# PIC_Schematic.net
KiCad netlist of a schematic drawn in Altium Designer
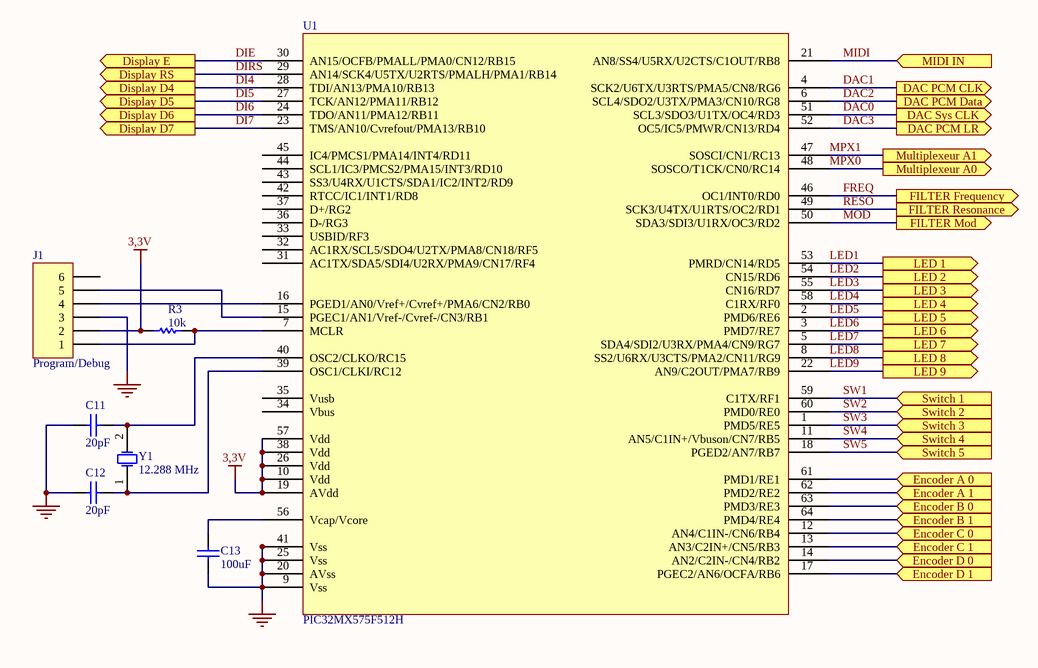
[diagram p0: PIC.Schematic.SchDoc]

(export (version "E")
  (design (tool "Eeschema 10.0.6"))
  (components
    (comp (ref "C11")
      (value "20pF")
      (footprint "CAP1608N")
      (description "Capacitor (Semiconductor SIM Model)")
      (fields (field (name "PUBLISHER") "Altium Limited"))
      (libsource (lib "Miscellaneous Devices") (part "Cap Semi"))
    )
    (comp (ref "C12")
      (value "20pF")
      (footprint "CAP1608N")
      (description "Capacitor (Semiconductor SIM Model)")
      (fields (field (name "PUBLISHER") "Altium Limited"))
      (libsource (lib "Miscellaneous Devices") (part "Cap Semi"))
    )
    (comp (ref "C13")
      (value "100uF")
      (footprint "RAD-0.3")
      (description "Capacitor")
      (fields (field (name "Comment") "Cap") (field (name "PUBLISHER") "Altium Limited"))
      (libsource (lib "Miscellaneous Devices") (part "Cap"))
    )
    (comp (ref "J1")
      (value "Program/Debug")
      (footprint "HDR1X6H")
      (description "Header, 6-Pin, Right Angle")
      (fields (field (name "PUBLISHER") "Altium Limited"))
      (libsource (lib "Miscellaneous Connectors") (part "Header 6H"))
    )
    (comp (ref "R3")
      (value "10k")
      (footprint "AXIAL-0.3")
      (description "Resistor")
      (fields (field (name "PUBLISHER") "Altium Limited"))
      (libsource (lib "Miscellaneous Devices") (part "Res1"))
    )
    (comp (ref "U1")
      (value "PIC32MX575F512H")
      (libsource (lib "SynthyTwo.Components") (part "PIC32 MX575F512H"))
    )
    (comp (ref "Y1")
      (value "12.288 MHz")
      (footprint "R38")
      (description "Crystal Oscillator")
      (fields (field (name "PUBLISHER") "Altium Limited"))
      (libsource (lib "Miscellaneous Devices") (part "XTAL"))
    )
  )
  (nets
    (net (code "1") (name "/DAC0") (class "Default")
      (node (ref "U1") (pin "51") (pinfunction "SCL3/SDO3/U1TX/OC4/RD3_51") (pintype "passive"))
    )
    (net (code "2") (name "/DAC1") (class "Default")
      (node (ref "U1") (pin "4") (pinfunction "SCK2/U6TX/U3RTS/PMA5/CN8/RG6_4") (pintype "passive"))
    )
    (net (code "3") (name "/DAC2") (class "Default")
      (node (ref "U1") (pin "6") (pinfunction "SCL4/SDO2/U3TX/PMA3/CN10/RG8_6") (pintype "passive"))
    )
    (net (code "4") (name "/DAC3") (class "Default")
      (node (ref "U1") (pin "52") (pinfunction "OC5/IC5/PMWR/CN13/RD4_52") (pintype "passive"))
    )
    (net (code "5") (name "/DI4") (class "Default")
      (node (ref "U1") (pin "28") (pinfunction "TDI/AN13/PMA10/RB13_28") (pintype "passive"))
    )
    (net (code "6") (name "/DI5") (class "Default")
      (node (ref "U1") (pin "27") (pinfunction "TCK/AN12/PMA11/RB12_27") (pintype "passive"))
    )
    (net (code "7") (name "/DI6") (class "Default")
      (node (ref "U1") (pin "24") (pinfunction "TDO/AN11/PMA12/RB11_24") (pintype "passive"))
    )
    (net (code "8") (name "/DI7") (class "Default")
      (node (ref "U1") (pin "23") (pinfunction "TMS/AN10/Cvrefout/PMA13/RB10_23") (pintype "passive"))
    )
    (net (code "9") (name "/DIE") (class "Default")
      (node (ref "U1") (pin "30") (pinfunction "AN15/OCFB/PMALL/PMA0/CN12/RB15_30") (pintype "passive"))
    )
    (net (code "10") (name "/DIRS") (class "Default")
      (node (ref "U1") (pin "29") (pinfunction "AN14/SCK4/U5TX/U2RTS/PMALH/PMA1/RB14_29") (pintype "passive"))
    )
    (net (code "11") (name "/Encoder A 0") (class "Default")
      (node (ref "U1") (pin "61") (pinfunction "PMD1/RE1_61") (pintype "passive"))
    )
    (net (code "12") (name "/Encoder A 1") (class "Default")
      (node (ref "U1") (pin "62") (pinfunction "PMD2/RE2_62") (pintype "passive"))
    )
    (net (code "13") (name "/Encoder B 0") (class "Default")
      (node (ref "U1") (pin "63") (pinfunction "PMD3/RE3_63") (pintype "passive"))
    )
    (net (code "14") (name "/Encoder B 1") (class "Default")
      (node (ref "U1") (pin "64") (pinfunction "PMD4/RE4_64") (pintype "passive"))
    )
    (net (code "15") (name "/Encoder C 0") (class "Default")
      (node (ref "U1") (pin "12") (pinfunction "AN4/C1IN-/CN6/RB4_12") (pintype "passive"))
    )
    (net (code "16") (name "/Encoder C 1") (class "Default")
      (node (ref "U1") (pin "13") (pinfunction "AN3/C2IN+/CN5/RB3_13") (pintype "passive"))
    )
    (net (code "17") (name "/Encoder D 0") (class "Default")
      (node (ref "U1") (pin "14") (pinfunction "AN2/C2IN-/CN4/RB2_14") (pintype "passive"))
    )
    (net (code "18") (name "/Encoder D 1") (class "Default")
      (node (ref "U1") (pin "17") (pinfunction "PGEC2/AN6/OCFA/RB6_17") (pintype "passive"))
    )
    (net (code "19") (name "/FREQ") (class "Default")
      (node (ref "U1") (pin "46") (pinfunction "OC1/INT0/RD0_46") (pintype "passive"))
    )
    (net (code "20") (name "/LED1") (class "Default")
      (node (ref "U1") (pin "53") (pinfunction "PMRD/CN14/RD5_53") (pintype "passive"))
    )
    (net (code "21") (name "/LED2") (class "Default")
      (node (ref "U1") (pin "54") (pinfunction "CN15/RD6_54") (pintype "passive"))
    )
    (net (code "22") (name "/LED3") (class "Default")
      (node (ref "U1") (pin "55") (pinfunction "CN16/RD7_55") (pintype "passive"))
    )
    (net (code "23") (name "/LED4") (class "Default")
      (node (ref "U1") (pin "58") (pinfunction "C1RX/RF0_58") (pintype "passive"))
    )
    (net (code "24") (name "/LED5") (class "Default")
      (node (ref "U1") (pin "2") (pinfunction "PMD6/RE6_2") (pintype "passive"))
    )
    (net (code "25") (name "/LED6") (class "Default")
      (node (ref "U1") (pin "3") (pinfunction "PMD7/RE7_3") (pintype "passive"))
    )
    (net (code "26") (name "/LED7") (class "Default")
      (node (ref "U1") (pin "5") (pinfunction "SDA4/SDI2/U3RX/PMA4/CN9/RG7_5") (pintype "passive"))
    )
    (net (code "27") (name "/LED8") (class "Default")
      (node (ref "U1") (pin "8") (pinfunction "SS2/U6RX/U3CTS/PMA2/CN11/RG9_8") (pintype "passive"))
    )
    (net (code "28") (name "/LED9") (class "Default")
      (node (ref "U1") (pin "22") (pinfunction "AN9/C2OUT/PMA7/RB9_22") (pintype "passive"))
    )
    (net (code "29") (name "/MIDI") (class "Default")
      (node (ref "U1") (pin "21") (pinfunction "AN8/SS4/U5RX/U2CTS/C1OUT/RB8_21") (pintype "passive"))
    )
    (net (code "30") (name "/MOD") (class "Default")
      (node (ref "U1") (pin "50") (pinfunction "SDA3/SDI3/U1RX/OC3/RD2_50") (pintype "passive"))
    )
    (net (code "31") (name "/MPX0") (class "Default")
      (node (ref "U1") (pin "48") (pinfunction "SOSCO/T1CK/CN0/RC14_48") (pintype "passive"))
    )
    (net (code "32") (name "/MPX1") (class "Default")
      (node (ref "U1") (pin "47") (pinfunction "SOSCI/CN1/RC13_47") (pintype "passive"))
    )
    (net (code "33") (name "/RESO") (class "Default")
      (node (ref "U1") (pin "49") (pinfunction "SCK3/U4TX/U1RTS/OC2/RD1_49") (pintype "passive"))
    )
    (net (code "34") (name "/SW1") (class "Default")
      (node (ref "U1") (pin "59") (pinfunction "C1TX/RF1_59") (pintype "passive"))
    )
    (net (code "35") (name "/SW2") (class "Default")
      (node (ref "U1") (pin "60") (pinfunction "PMD0/RE0_60") (pintype "passive"))
    )
    (net (code "36") (name "/SW3") (class "Default")
      (node (ref "U1") (pin "1") (pinfunction "PMD5/RE5_1") (pintype "passive"))
    )
    (net (code "37") (name "/SW4") (class "Default")
      (node (ref "U1") (pin "11") (pinfunction "AN5/C1IN+/Vbuson/CN7/RB5_11") (pintype "passive"))
    )
    (net (code "38") (name "/SW5") (class "Default")
      (node (ref "U1") (pin "18") (pinfunction "PGED2/AN7/RB7_18") (pintype "passive"))
    )
    (net (code "39") (name "3,3V") (class "Default")
      (node (ref "J1") (pin "2") (pinfunction "2_2") (pintype "passive"))
      (node (ref "R3") (pin "2") (pinfunction "2_2") (pintype "passive"))
      (node (ref "U1") (pin "10") (pinfunction "Vdd_10") (pintype "passive"))
      (node (ref "U1") (pin "19") (pinfunction "AVdd_19") (pintype "passive"))
      (node (ref "U1") (pin "26") (pinfunction "Vdd_26") (pintype "passive"))
      (node (ref "U1") (pin "38") (pinfunction "Vdd_38") (pintype "passive"))
      (node (ref "U1") (pin "57") (pinfunction "Vdd_57") (pintype "passive"))
    )
    (net (code "40") (name "GND") (class "Default")
      (node (ref "C11") (pin "1") (pinfunction "1_1") (pintype "passive"))
      (node (ref "C12") (pin "1") (pinfunction "1_1") (pintype "passive"))
      (node (ref "C13") (pin "1") (pinfunction "1_1") (pintype "passive"))
      (node (ref "J1") (pin "3") (pinfunction "3_3") (pintype "passive"))
      (node (ref "U1") (pin "20") (pinfunction "AVss_20") (pintype "passive"))
      (node (ref "U1") (pin "25") (pinfunction "Vss_25") (pintype "passive"))
      (node (ref "U1") (pin "41") (pinfunction "Vss_41") (pintype "passive"))
      (node (ref "U1") (pin "9") (pinfunction "Vss_9") (pintype "passive"))
    )
    (net (code "41") (name "Net-(U1-MCLR)") (class "Default")
      (node (ref "J1") (pin "1") (pinfunction "1_1") (pintype "passive"))
      (node (ref "R3") (pin "1") (pinfunction "1_1") (pintype "passive"))
      (node (ref "U1") (pin "7") (pinfunction "MCLR_7") (pintype "passive"))
    )
    (net (code "42") (name "Net-(U1-OSC1{slash}CLKI{slash}RC12)") (class "Default")
      (node (ref "C12") (pin "2") (pinfunction "2_2") (pintype "passive"))
      (node (ref "U1") (pin "39") (pinfunction "OSC1/CLKI/RC12_39") (pintype "passive"))
      (node (ref "Y1") (pin "1") (pinfunction "OSC1_1") (pintype "passive"))
    )
    (net (code "43") (name "Net-(U1-OSC2{slash}CLKO{slash}RC15)") (class "Default")
      (node (ref "C11") (pin "2") (pinfunction "2_2") (pintype "passive"))
      (node (ref "U1") (pin "40") (pinfunction "OSC2/CLKO/RC15_40") (pintype "passive"))
      (node (ref "Y1") (pin "2") (pinfunction "OSC2_2") (pintype "passive"))
    )
    (net (code "44") (name "Net-(U1-PGEC1{slash}AN1{slash}Vref-{slash}Cvref-{slash}CN3{slash}RB1)") (class "Default")
      (node (ref "J1") (pin "5") (pinfunction "5_5") (pintype "passive"))
      (node (ref "U1") (pin "15") (pinfunction "PGEC1/AN1/Vref-/Cvref-/CN3/RB1_15") (pintype "passive"))
    )
    (net (code "45") (name "Net-(U1-PGED1{slash}AN0{slash}Vref+{slash}Cvref+{slash}PMA6{slash}CN2{slash}RB0)") (class "Default")
      (node (ref "J1") (pin "4") (pinfunction "4_4") (pintype "passive"))
      (node (ref "U1") (pin "16") (pinfunction "PGED1/AN0/Vref+/Cvref+/PMA6/CN2/RB0_16") (pintype "passive"))
    )
    (net (code "46") (name "Net-(U1-Vcap{slash}Vcore)") (class "Default")
      (node (ref "C13") (pin "2") (pinfunction "2_2") (pintype "passive"))
      (node (ref "U1") (pin "56") (pinfunction "Vcap/Vcore_56") (pintype "passive"))
    )
    (net (code "47") (name "unconnected-(J1-Pad6)") (class "Default")
      (node (ref "J1") (pin "6") (pinfunction "6_6") (pintype "passive"))
    )
    (net (code "48") (name "unconnected-(U1-AC1RX{slash}SCL5{slash}SDO4{slash}U2TX{slash}PMA8{slash}CN18{slash}RF5-Pad32)") (class "Default")
      (node (ref "U1") (pin "32") (pinfunction "AC1RX/SCL5/SDO4/U2TX/PMA8/CN18/RF5_32") (pintype "passive"))
    )
    (net (code "49") (name "unconnected-(U1-AC1TX{slash}SDA5{slash}SDI4{slash}U2RX{slash}PMA9{slash}CN17{slash}RF4-Pad31)") (class "Default")
      (node (ref "U1") (pin "31") (pinfunction "AC1TX/SDA5/SDI4/U2RX/PMA9/CN17/RF4_31") (pintype "passive"))
    )
    (net (code "50") (name "unconnected-(U1-D+{slash}RG2-Pad37)") (class "Default")
      (node (ref "U1") (pin "37") (pinfunction "D+/RG2_37") (pintype "passive"))
    )
    (net (code "51") (name "unconnected-(U1-D-{slash}RG3-Pad36)") (class "Default")
      (node (ref "U1") (pin "36") (pinfunction "D-/RG3_36") (pintype "passive"))
    )
    (net (code "52") (name "unconnected-(U1-IC4{slash}PMCS1{slash}PMA14{slash}INT4{slash}RD11-Pad45)") (class "Default")
      (node (ref "U1") (pin "45") (pinfunction "IC4/PMCS1/PMA14/INT4/RD11_45") (pintype "passive"))
    )
    (net (code "53") (name "unconnected-(U1-RTCC{slash}IC1{slash}INT1{slash}RD8-Pad42)") (class "Default")
      (node (ref "U1") (pin "42") (pinfunction "RTCC/IC1/INT1/RD8_42") (pintype "passive"))
    )
    (net (code "54") (name "unconnected-(U1-SCL1{slash}IC3{slash}PMCS2{slash}PMA15{slash}INT3{slash}RD10-Pad44)") (class "Default")
      (node (ref "U1") (pin "44") (pinfunction "SCL1/IC3/PMCS2/PMA15/INT3/RD10_44") (pintype "passive"))
    )
    (net (code "55") (name "unconnected-(U1-SS3{slash}U4RX{slash}U1CTS{slash}SDA1{slash}IC2{slash}INT2{slash}RD9-Pad43)") (class "Default")
      (node (ref "U1") (pin "43") (pinfunction "SS3/U4RX/U1CTS/SDA1/IC2/INT2/RD9_43") (pintype "passive"))
    )
    (net (code "56") (name "unconnected-(U1-USBID{slash}RF3-Pad33)") (class "Default")
      (node (ref "U1") (pin "33") (pinfunction "USBID/RF3_33") (pintype "passive"))
    )
    (net (code "57") (name "unconnected-(U1-Vbus-Pad34)") (class "Default")
      (node (ref "U1") (pin "34") (pinfunction "Vbus_34") (pintype "passive"))
    )
    (net (code "58") (name "unconnected-(U1-Vusb-Pad35)") (class "Default")
      (node (ref "U1") (pin "35") (pinfunction "Vusb_35") (pintype "passive"))
    )
  )
)
